# experimental.net
KiCad netlist of a schematic drawn in Altium Designer
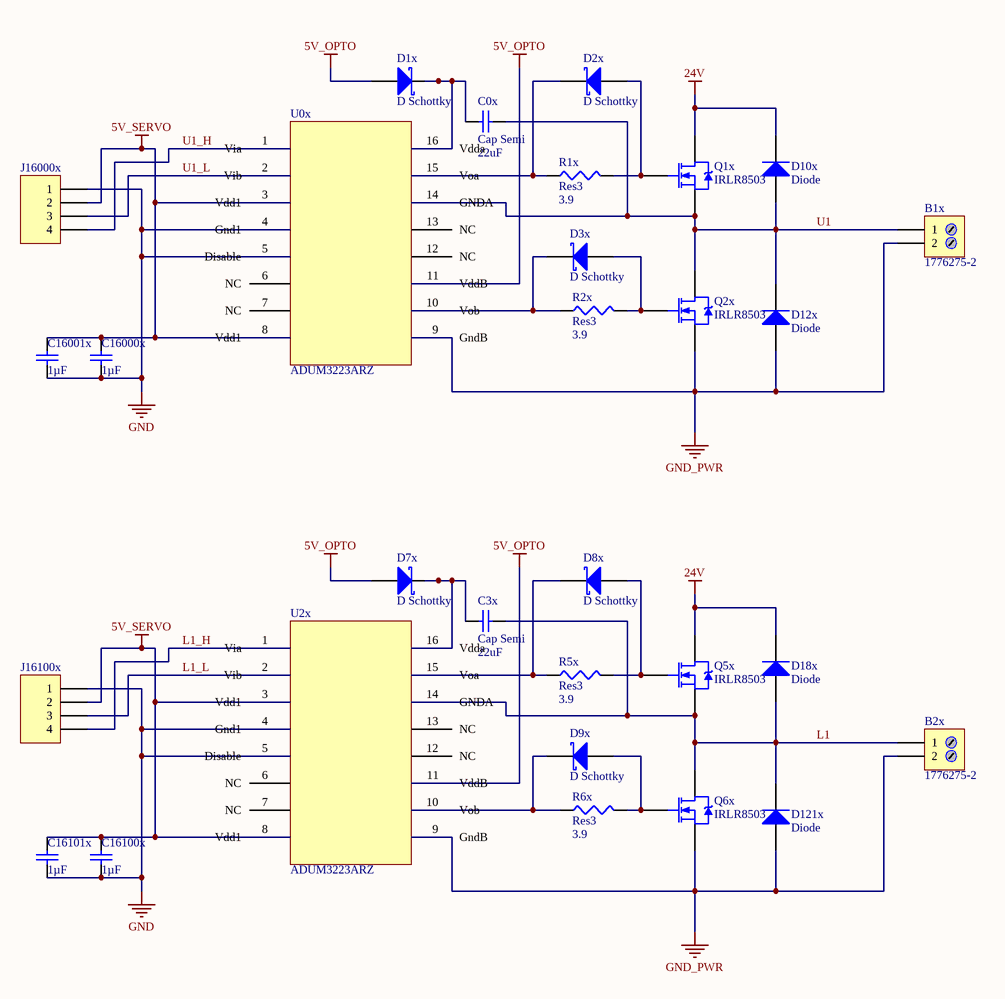
[diagram p0: experimental.SchDoc]

(export (version "E")
  (design (tool "Eeschema 10.0.6"))
  (components
    (comp (ref "B1x")
      (value "1776275-2")
      (footprint "BORNIER_2V_3.5MM")
      (description "TERM BLOCK 2POS SIDE ENT 3.5MM")
      (fields (field (name "MANUFACTURER") "TE Connectivity AMP Connectors"))
      (libsource (lib "Divers") (part "1776275-2"))
    )
    (comp (ref "B2x")
      (value "1776275-2")
      (footprint "BORNIER_2V_3.5MM")
      (description "TERM BLOCK 2POS SIDE ENT 3.5MM")
      (fields (field (name "MANUFACTURER") "TE Connectivity AMP Connectors"))
      (libsource (lib "Divers") (part "1776275-2"))
    )
    (comp (ref "C0x")
      (value "Cap Semi")
      (footprint "C1210")
      (description "Capacitor (Semiconductor SIM Model)")
      (fields (field (name "ALTIUM_VALUE") "22uF") (field (name "PUBLISHER") "Altium Limited"))
      (libsource (lib "Miscellaneous Devices") (part "Cap Semi"))
    )
    (comp (ref "C3x")
      (value "Cap Semi")
      (footprint "C1210")
      (description "Capacitor (Semiconductor SIM Model)")
      (fields (field (name "ALTIUM_VALUE") "22uF") (field (name "PUBLISHER") "Altium Limited"))
      (libsource (lib "Miscellaneous Devices") (part "Cap Semi"))
    )
    (comp (ref "C16000x")
      (value "1µF")
      (footprint "WCAP-CSGP_0603, 1.6x0.8x0.8")
      (description "CAP CER 100nF 50V X7R 0603")
      (fields
        (field (name "MANUFACTURER") "Wurth Elektronik")
        (field (name "MANUFACTURER PART NUMBER") "885012206095")
      )
      (libsource (lib "Condensateur") (part "WCAP-CSGP, 885012206095"))
    )
    (comp (ref "C16001x")
      (value "1µF")
      (footprint "WCAP-CSGP_0603, 1.6x0.8x0.8")
      (description "CAP CER 100nF 50V X7R 0603")
      (fields
        (field (name "MANUFACTURER") "Wurth Elektronik")
        (field (name "MANUFACTURER PART NUMBER") "885012206095")
      )
      (libsource (lib "Condensateur") (part "WCAP-CSGP, 885012206095"))
    )
    (comp (ref "C16100x")
      (value "1µF")
      (footprint "WCAP-CSGP_0603, 1.6x0.8x0.8")
      (description "CAP CER 100nF 50V X7R 0603")
      (fields
        (field (name "MANUFACTURER") "Wurth Elektronik")
        (field (name "MANUFACTURER PART NUMBER") "885012206095")
      )
      (libsource (lib "Condensateur") (part "WCAP-CSGP, 885012206095"))
    )
    (comp (ref "C16101x")
      (value "1µF")
      (footprint "WCAP-CSGP_0603, 1.6x0.8x0.8")
      (description "CAP CER 100nF 50V X7R 0603")
      (fields
        (field (name "MANUFACTURER") "Wurth Elektronik")
        (field (name "MANUFACTURER PART NUMBER") "885012206095")
      )
      (libsource (lib "Condensateur") (part "WCAP-CSGP, 885012206095"))
    )
    (comp (ref "D1x")
      (value "D Schottky")
      (footprint "SMB")
      (description "Schottky Diode")
      (fields (field (name "PUBLISHER") "Altium Limited"))
      (libsource (lib "Miscellaneous Devices") (part "D Schottky"))
    )
    (comp (ref "D2x")
      (value "D Schottky")
      (footprint "SMB")
      (description "Schottky Diode")
      (fields (field (name "PUBLISHER") "Altium Limited"))
      (libsource (lib "Miscellaneous Devices") (part "D Schottky"))
    )
    (comp (ref "D3x")
      (value "D Schottky")
      (footprint "SMB")
      (description "Schottky Diode")
      (fields (field (name "PUBLISHER") "Altium Limited"))
      (libsource (lib "Miscellaneous Devices") (part "D Schottky"))
    )
    (comp (ref "D7x")
      (value "D Schottky")
      (footprint "SMB")
      (description "Schottky Diode")
      (fields (field (name "PUBLISHER") "Altium Limited"))
      (libsource (lib "Miscellaneous Devices") (part "D Schottky"))
    )
    (comp (ref "D8x")
      (value "D Schottky")
      (footprint "SMB")
      (description "Schottky Diode")
      (fields (field (name "PUBLISHER") "Altium Limited"))
      (libsource (lib "Miscellaneous Devices") (part "D Schottky"))
    )
    (comp (ref "D9x")
      (value "D Schottky")
      (footprint "SMB")
      (description "Schottky Diode")
      (fields (field (name "PUBLISHER") "Altium Limited"))
      (libsource (lib "Miscellaneous Devices") (part "D Schottky"))
    )
    (comp (ref "D10x")
      (value "Diode")
      (footprint "SMC")
      (description "Default Diode")
      (fields (field (name "PUBLISHER") "Altium Limited"))
      (libsource (lib "Miscellaneous Devices") (part "Diode"))
    )
    (comp (ref "D12x")
      (value "Diode")
      (footprint "SMC")
      (description "Default Diode")
      (fields (field (name "PUBLISHER") "Altium Limited"))
      (libsource (lib "Miscellaneous Devices") (part "Diode"))
    )
    (comp (ref "D18x")
      (value "Diode")
      (footprint "SMC")
      (description "Default Diode")
      (fields (field (name "PUBLISHER") "Altium Limited"))
      (libsource (lib "Miscellaneous Devices") (part "Diode"))
    )
    (comp (ref "D121x")
      (value "Diode")
      (footprint "SMC")
      (description "Default Diode")
      (fields (field (name "PUBLISHER") "Altium Limited"))
      (libsource (lib "Miscellaneous Devices") (part "Diode"))
    )
    (comp (ref "J16000x")
      (value "MC34645")
      (footprint "HDR1X4")
      (description "MULTICOMP - MC34645 - EMB. MALE COUDEE  CON. MALE 2.54MM 4VOIE")
      (fields (field (name "MANUFACTURER") "MULTICOMP"))
      (libsource (lib "Connecteurs") (part "MC34645"))
    )
    (comp (ref "J16100x")
      (value "MC34645")
      (footprint "HDR1X4")
      (description "MULTICOMP - MC34645 - EMB. MALE COUDEE  CON. MALE 2.54MM 4VOIE")
      (fields (field (name "MANUFACTURER") "MULTICOMP"))
      (libsource (lib "Connecteurs") (part "MC34645"))
    )
    (comp (ref "Q1x")
      (value "IRLR8503")
      (footprint "TO-252AA")
      (description "HEXFET Power MOSFET")
      (fields (field (name "PUBLISHER") "Altium Limited"))
      (libsource (lib "Divers_goldo") (part "IRLR8503"))
    )
    (comp (ref "Q2x")
      (value "IRLR8503")
      (footprint "TO-252AA")
      (description "HEXFET Power MOSFET")
      (fields (field (name "PUBLISHER") "Altium Limited"))
      (libsource (lib "Divers_goldo") (part "IRLR8503"))
    )
    (comp (ref "Q5x")
      (value "IRLR8503")
      (footprint "TO-252AA")
      (description "HEXFET Power MOSFET")
      (fields (field (name "PUBLISHER") "Altium Limited"))
      (libsource (lib "Divers_goldo") (part "IRLR8503"))
    )
    (comp (ref "Q6x")
      (value "IRLR8503")
      (footprint "TO-252AA")
      (description "HEXFET Power MOSFET")
      (fields (field (name "PUBLISHER") "Altium Limited"))
      (libsource (lib "Divers_goldo") (part "IRLR8503"))
    )
    (comp (ref "R1x")
      (value "Res3")
      (footprint "14-1210")
      (description "Resistor")
      (fields (field (name "ALTIUM_VALUE") "3.9") (field (name "PUBLISHER") "Altium Limited"))
      (libsource (lib "Miscellaneous Devices") (part "Res3"))
    )
    (comp (ref "R2x")
      (value "Res3")
      (footprint "14-1210")
      (description "Resistor")
      (fields (field (name "ALTIUM_VALUE") "3.9") (field (name "PUBLISHER") "Altium Limited"))
      (libsource (lib "Miscellaneous Devices") (part "Res3"))
    )
    (comp (ref "R5x")
      (value "Res3")
      (footprint "14-1210")
      (description "Resistor")
      (fields (field (name "ALTIUM_VALUE") "3.9") (field (name "PUBLISHER") "Altium Limited"))
      (libsource (lib "Miscellaneous Devices") (part "Res3"))
    )
    (comp (ref "R6x")
      (value "Res3")
      (footprint "14-1210")
      (description "Resistor")
      (fields (field (name "ALTIUM_VALUE") "3.9") (field (name "PUBLISHER") "Altium Limited"))
      (libsource (lib "Miscellaneous Devices") (part "Res3"))
    )
    (comp (ref "U0x")
      (value "ADUM3223ARZ")
      (footprint "SOIC16_N")
      (libsource (lib "ADUM3223ARZ") (part "ADUM3223ARZ"))
    )
    (comp (ref "U2x")
      (value "ADUM3223ARZ")
      (footprint "SOIC16_N")
      (libsource (lib "ADUM3223ARZ") (part "ADUM3223ARZ"))
    )
  )
  (nets
    (net (code "1") (name "/L1") (class "Default")
      (node (ref "B2x") (pin "1") (pinfunction "1_1") (pintype "passive"))
      (node (ref "C3x") (pin "2") (pinfunction "2_2") (pintype "passive"))
      (node (ref "D121x") (pin "2") (pinfunction "K_2") (pintype "passive"))
      (node (ref "D18x") (pin "1") (pinfunction "A_1") (pintype "passive"))
      (node (ref "Q5x") (pin "3") (pinfunction "S_3") (pintype "passive"))
      (node (ref "Q6x") (pin "4") (pinfunction "D_4") (pintype "passive"))
      (node (ref "U2x") (pin "14") (pinfunction "GNDA_14") (pintype "passive"))
    )
    (net (code "2") (name "/L1_H") (class "Default")
      (node (ref "J16100x") (pin "4") (pinfunction "4_4") (pintype "passive"))
      (node (ref "U2x") (pin "1") (pinfunction "Via_1") (pintype "passive"))
    )
    (net (code "3") (name "/L1_L") (class "Default")
      (node (ref "J16100x") (pin "3") (pinfunction "3_3") (pintype "passive"))
      (node (ref "U2x") (pin "2") (pinfunction "Vib_2") (pintype "passive"))
    )
    (net (code "4") (name "/U1") (class "Default")
      (node (ref "B1x") (pin "1") (pinfunction "1_1") (pintype "passive"))
      (node (ref "C0x") (pin "2") (pinfunction "2_2") (pintype "passive"))
      (node (ref "D10x") (pin "1") (pinfunction "A_1") (pintype "passive"))
      (node (ref "D12x") (pin "2") (pinfunction "K_2") (pintype "passive"))
      (node (ref "Q1x") (pin "3") (pinfunction "S_3") (pintype "passive"))
      (node (ref "Q2x") (pin "4") (pinfunction "D_4") (pintype "passive"))
      (node (ref "U0x") (pin "14") (pinfunction "GNDA_14") (pintype "passive"))
    )
    (net (code "5") (name "/U1_H") (class "Default")
      (node (ref "J16000x") (pin "4") (pinfunction "4_4") (pintype "passive"))
      (node (ref "U0x") (pin "1") (pinfunction "Via_1") (pintype "passive"))
    )
    (net (code "6") (name "/U1_L") (class "Default")
      (node (ref "J16000x") (pin "3") (pinfunction "3_3") (pintype "passive"))
      (node (ref "U0x") (pin "2") (pinfunction "Vib_2") (pintype "passive"))
    )
    (net (code "7") (name "5V_OPTO") (class "Default")
      (node (ref "D1x") (pin "1") (pinfunction "A_1") (pintype "passive"))
      (node (ref "D7x") (pin "1") (pinfunction "A_1") (pintype "passive"))
      (node (ref "U0x") (pin "11") (pinfunction "VddB_11") (pintype "passive"))
      (node (ref "U2x") (pin "11") (pinfunction "VddB_11") (pintype "passive"))
    )
    (net (code "8") (name "5V_SERVO") (class "Default")
      (node (ref "C16000x") (pin "1") (pinfunction "1_1") (pintype "passive"))
      (node (ref "C16001x") (pin "1") (pinfunction "1_1") (pintype "passive"))
      (node (ref "C16100x") (pin "1") (pinfunction "1_1") (pintype "passive"))
      (node (ref "C16101x") (pin "1") (pinfunction "1_1") (pintype "passive"))
      (node (ref "J16000x") (pin "2") (pinfunction "2_2") (pintype "passive"))
      (node (ref "J16100x") (pin "2") (pinfunction "2_2") (pintype "passive"))
      (node (ref "U0x") (pin "3") (pinfunction "Vdd1_3") (pintype "passive"))
      (node (ref "U0x") (pin "8") (pinfunction "Vdd1_8") (pintype "passive"))
      (node (ref "U2x") (pin "3") (pinfunction "Vdd1_3") (pintype "passive"))
      (node (ref "U2x") (pin "8") (pinfunction "Vdd1_8") (pintype "passive"))
    )
    (net (code "9") (name "24V") (class "Default")
      (node (ref "D10x") (pin "2") (pinfunction "K_2") (pintype "passive"))
      (node (ref "D18x") (pin "2") (pinfunction "K_2") (pintype "passive"))
      (node (ref "Q1x") (pin "4") (pinfunction "D_4") (pintype "passive"))
      (node (ref "Q5x") (pin "4") (pinfunction "D_4") (pintype "passive"))
    )
    (net (code "10") (name "GND") (class "Default")
      (node (ref "C16000x") (pin "2") (pinfunction "2_2") (pintype "passive"))
      (node (ref "C16001x") (pin "2") (pinfunction "2_2") (pintype "passive"))
      (node (ref "C16100x") (pin "2") (pinfunction "2_2") (pintype "passive"))
      (node (ref "C16101x") (pin "2") (pinfunction "2_2") (pintype "passive"))
      (node (ref "J16000x") (pin "1") (pinfunction "1_1") (pintype "passive"))
      (node (ref "J16100x") (pin "1") (pinfunction "1_1") (pintype "passive"))
      (node (ref "U0x") (pin "4") (pinfunction "Gnd1_4") (pintype "passive"))
      (node (ref "U0x") (pin "5") (pinfunction "Disable_5") (pintype "passive"))
      (node (ref "U2x") (pin "4") (pinfunction "Gnd1_4") (pintype "passive"))
      (node (ref "U2x") (pin "5") (pinfunction "Disable_5") (pintype "passive"))
    )
    (net (code "11") (name "GND_PWR") (class "Default")
      (node (ref "B1x") (pin "2") (pinfunction "2_2") (pintype "passive"))
      (node (ref "B2x") (pin "2") (pinfunction "2_2") (pintype "passive"))
      (node (ref "D121x") (pin "1") (pinfunction "A_1") (pintype "passive"))
      (node (ref "D12x") (pin "1") (pinfunction "A_1") (pintype "passive"))
      (node (ref "Q2x") (pin "3") (pinfunction "S_3") (pintype "passive"))
      (node (ref "Q6x") (pin "3") (pinfunction "S_3") (pintype "passive"))
      (node (ref "U0x") (pin "9") (pinfunction "GndB_9") (pintype "passive"))
      (node (ref "U2x") (pin "9") (pinfunction "GndB_9") (pintype "passive"))
    )
    (net (code "12") (name "Net-(D1x-K)") (class "Default")
      (node (ref "C0x") (pin "1") (pinfunction "1_1") (pintype "passive"))
      (node (ref "D1x") (pin "2") (pinfunction "K_2") (pintype "passive"))
      (node (ref "U0x") (pin "16") (pinfunction "Vdda_16") (pintype "passive"))
    )
    (net (code "13") (name "Net-(D2x-A)") (class "Default")
      (node (ref "D2x") (pin "1") (pinfunction "A_1") (pintype "passive"))
      (node (ref "Q1x") (pin "1") (pinfunction "G_1") (pintype "passive"))
      (node (ref "R1x") (pin "2") (pinfunction "2_2") (pintype "passive"))
    )
    (net (code "14") (name "Net-(D2x-K)") (class "Default")
      (node (ref "D2x") (pin "2") (pinfunction "K_2") (pintype "passive"))
      (node (ref "R1x") (pin "1") (pinfunction "1_1") (pintype "passive"))
      (node (ref "U0x") (pin "15") (pinfunction "Voa_15") (pintype "passive"))
    )
    (net (code "15") (name "Net-(D3x-A)") (class "Default")
      (node (ref "D3x") (pin "1") (pinfunction "A_1") (pintype "passive"))
      (node (ref "Q2x") (pin "1") (pinfunction "G_1") (pintype "passive"))
      (node (ref "R2x") (pin "2") (pinfunction "2_2") (pintype "passive"))
    )
    (net (code "16") (name "Net-(D3x-K)") (class "Default")
      (node (ref "D3x") (pin "2") (pinfunction "K_2") (pintype "passive"))
      (node (ref "R2x") (pin "1") (pinfunction "1_1") (pintype "passive"))
      (node (ref "U0x") (pin "10") (pinfunction "Vob_10") (pintype "passive"))
    )
    (net (code "17") (name "Net-(D7x-K)") (class "Default")
      (node (ref "C3x") (pin "1") (pinfunction "1_1") (pintype "passive"))
      (node (ref "D7x") (pin "2") (pinfunction "K_2") (pintype "passive"))
      (node (ref "U2x") (pin "16") (pinfunction "Vdda_16") (pintype "passive"))
    )
    (net (code "18") (name "Net-(D8x-A)") (class "Default")
      (node (ref "D8x") (pin "1") (pinfunction "A_1") (pintype "passive"))
      (node (ref "Q5x") (pin "1") (pinfunction "G_1") (pintype "passive"))
      (node (ref "R5x") (pin "2") (pinfunction "2_2") (pintype "passive"))
    )
    (net (code "19") (name "Net-(D8x-K)") (class "Default")
      (node (ref "D8x") (pin "2") (pinfunction "K_2") (pintype "passive"))
      (node (ref "R5x") (pin "1") (pinfunction "1_1") (pintype "passive"))
      (node (ref "U2x") (pin "15") (pinfunction "Voa_15") (pintype "passive"))
    )
    (net (code "20") (name "Net-(D9x-A)") (class "Default")
      (node (ref "D9x") (pin "1") (pinfunction "A_1") (pintype "passive"))
      (node (ref "Q6x") (pin "1") (pinfunction "G_1") (pintype "passive"))
      (node (ref "R6x") (pin "2") (pinfunction "2_2") (pintype "passive"))
    )
    (net (code "21") (name "Net-(D9x-K)") (class "Default")
      (node (ref "D9x") (pin "2") (pinfunction "K_2") (pintype "passive"))
      (node (ref "R6x") (pin "1") (pinfunction "1_1") (pintype "passive"))
      (node (ref "U2x") (pin "10") (pinfunction "Vob_10") (pintype "passive"))
    )
    (net (code "22") (name "unconnected-(U0x-NC-Pad6)") (class "Default")
      (node (ref "U0x") (pin "6") (pinfunction "NC_6") (pintype "passive"))
    )
    (net (code "23") (name "unconnected-(U0x-NC-Pad7)") (class "Default")
      (node (ref "U0x") (pin "7") (pinfunction "NC_7") (pintype "passive"))
    )
    (net (code "24") (name "unconnected-(U0x-NC-Pad12)") (class "Default")
      (node (ref "U0x") (pin "12") (pinfunction "NC_12") (pintype "passive"))
    )
    (net (code "25") (name "unconnected-(U0x-NC-Pad13)") (class "Default")
      (node (ref "U0x") (pin "13") (pinfunction "NC_13") (pintype "passive"))
    )
    (net (code "26") (name "unconnected-(U2x-NC-Pad6)") (class "Default")
      (node (ref "U2x") (pin "6") (pinfunction "NC_6") (pintype "passive"))
    )
    (net (code "27") (name "unconnected-(U2x-NC-Pad7)") (class "Default")
      (node (ref "U2x") (pin "7") (pinfunction "NC_7") (pintype "passive"))
    )
    (net (code "28") (name "unconnected-(U2x-NC-Pad12)") (class "Default")
      (node (ref "U2x") (pin "12") (pinfunction "NC_12") (pintype "passive"))
    )
    (net (code "29") (name "unconnected-(U2x-NC-Pad13)") (class "Default")
      (node (ref "U2x") (pin "13") (pinfunction "NC_13") (pintype "passive"))
    )
  )
)
